# Hambmark_PCB-practice-STM32-two-wheel-ba.net
KiCad netlist of a schematic drawn in Altium Designer
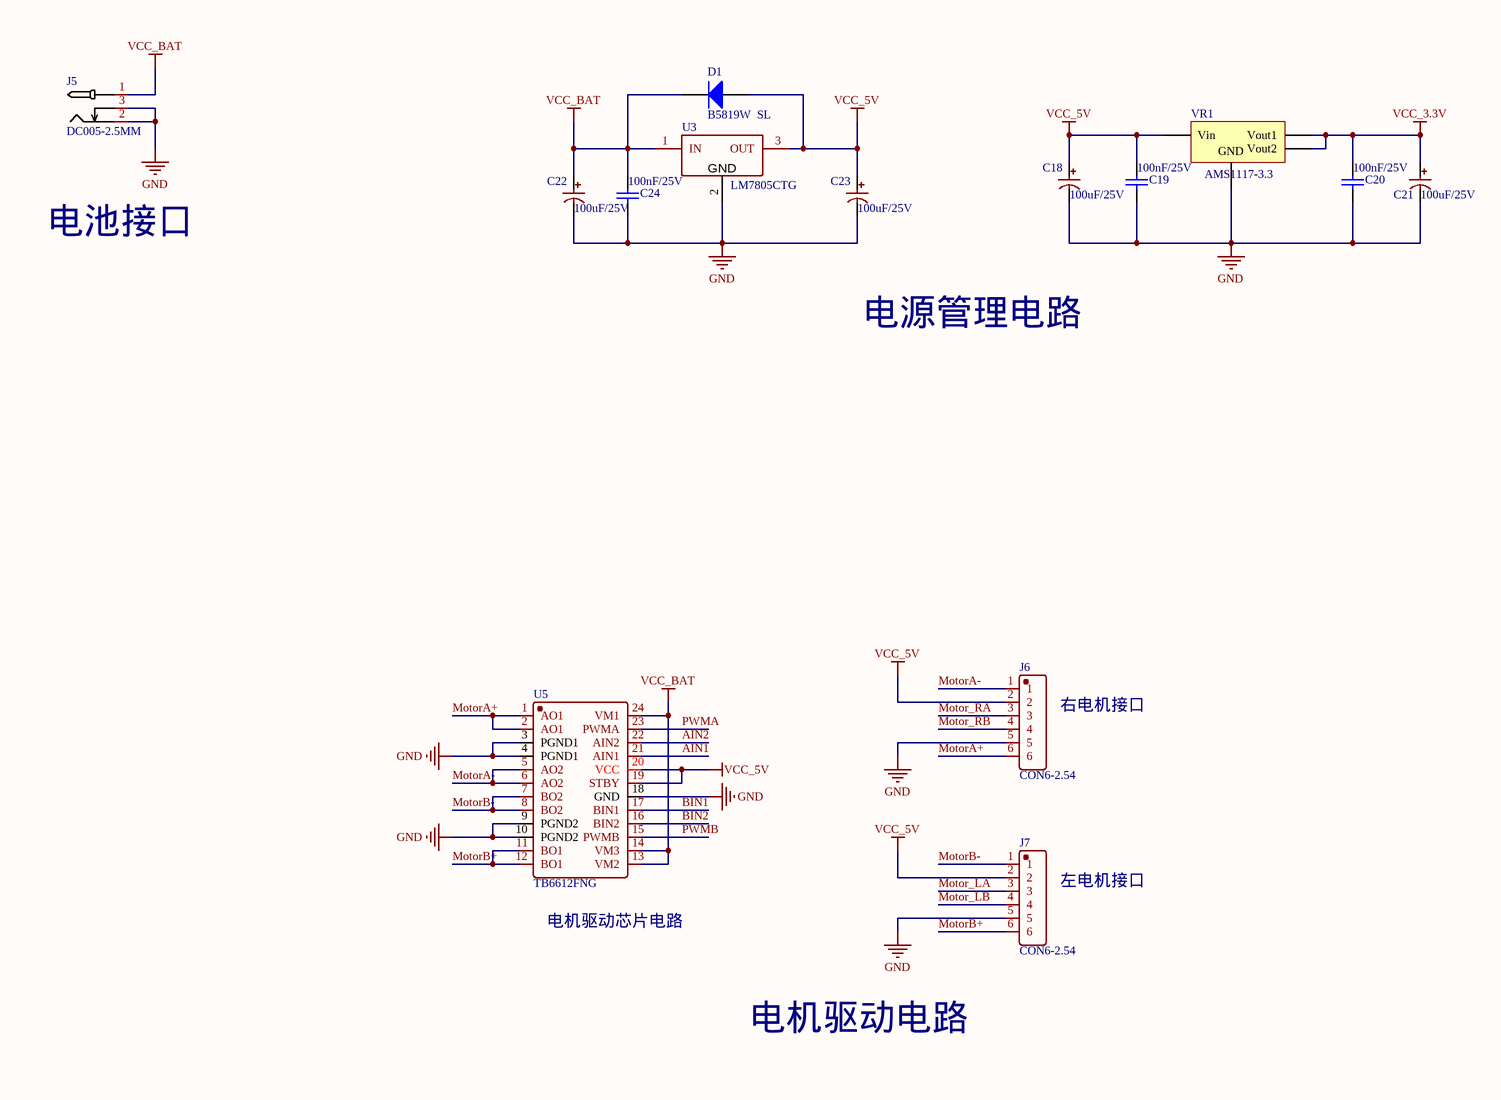
[diagram p0: Hambmark_PCB-practice-STM32-two-wheel-balancing-car__PRJ__1_Power.SchDoc]

(export (version "E")
  (design (tool "Eeschema 10.0.6"))
  (components
    (comp (ref "C18") (value "100uF/25V") (footprint "C0603") (libsource (lib "Other") (part "100uF/25V")))
    (comp (ref "C19")
      (value "100nF/25V")
      (footprint "C0603")
      (description "贴片电容")
      (libsource (lib "Cap") (part "0805 100nF(104) 10% 50V"))
    )
    (comp (ref "C20")
      (value "100nF/25V")
      (footprint "C0603")
      (description "贴片电容")
      (libsource (lib "Cap") (part "0805 100nF(104) 10% 50V"))
    )
    (comp (ref "C21") (value "100uF/25V") (footprint "C0603") (libsource (lib "Other") (part "100uF/25V")))
    (comp (ref "C22") (value "100uF/25V") (footprint "C0603") (libsource (lib "Other") (part "100uF/25V")))
    (comp (ref "C23") (value "100uF/25V") (footprint "C0603") (libsource (lib "Other") (part "100uF/25V")))
    (comp (ref "C24")
      (value "100nF/25V")
      (footprint "C0603")
      (description "贴片电容")
      (libsource (lib "Cap") (part "0805 100nF(104) 10% 50V"))
    )
    (comp (ref "D1")
      (value "B5819W  SL")
      (footprint "SOD-123")
      (description "肖特基二极管")
      (libsource (lib "Diode") (part "SOD-123 B5819W  SL"))
    )
    (comp (ref "J5")
      (value "DC005-2.5MM")
      (footprint "DC-IN-TH_DC005")
      (libsource (lib "Other") (part "DC005-2.5MM"))
    )
    (comp (ref "J6")
      (value "CON6-2.54")
      (footprint "HDR-TH_6P-P2.54-V-M")
      (libsource (lib "Other") (part "CON6-2.54"))
    )
    (comp (ref "J7")
      (value "CON6-2.54")
      (footprint "HDR-TH_6P-P2.54-V-M")
      (libsource (lib "Other") (part "CON6-2.54"))
    )
    (comp (ref "U3")
      (value "LM7805CTG")
      (footprint "TO-220-3_L10.2-W4.5-P2.54-L")
      (libsource (lib "Other") (part "LM7805CTG"))
    )
    (comp (ref "U5")
      (value "TB6612FNG")
      (footprint "SSOP-24_L8.4-W5.8-P0.65-LS7.8-BL")
      (libsource (lib "Other") (part "TB6612FNG"))
    )
    (comp (ref "VR1")
      (value "AMS1117-3.3")
      (footprint "SOT-223")
      (description "低压差线性稳压(LDO)")
      (libsource (lib "LDO") (part "SOT-223 AMS1117-3.3"))
    )
  )
  (nets
    (net (code "1") (name "/AIN1") (class "Default")
      (node (ref "U5") (pin "21") (pinfunction "AIN1_21") (pintype "passive"))
    )
    (net (code "2") (name "/AIN2") (class "Default")
      (node (ref "U5") (pin "22") (pinfunction "AIN2_22") (pintype "passive"))
    )
    (net (code "3") (name "/BIN1") (class "Default")
      (node (ref "U5") (pin "17") (pinfunction "BIN1_17") (pintype "passive"))
    )
    (net (code "4") (name "/BIN2") (class "Default")
      (node (ref "U5") (pin "16") (pinfunction "BIN2_16") (pintype "passive"))
    )
    (net (code "5") (name "/MotorA+") (class "Default")
      (node (ref "J6") (pin "6") (pinfunction "6_6") (pintype "passive"))
      (node (ref "U5") (pin "1") (pinfunction "AO1_1") (pintype "passive"))
      (node (ref "U5") (pin "2") (pinfunction "AO1_2") (pintype "passive"))
    )
    (net (code "6") (name "/MotorA-") (class "Default")
      (node (ref "J6") (pin "1") (pinfunction "1_1") (pintype "passive"))
      (node (ref "U5") (pin "5") (pinfunction "AO2_5") (pintype "passive"))
      (node (ref "U5") (pin "6") (pinfunction "AO2_6") (pintype "passive"))
    )
    (net (code "7") (name "/MotorB+") (class "Default")
      (node (ref "J7") (pin "6") (pinfunction "6_6") (pintype "passive"))
      (node (ref "U5") (pin "11") (pinfunction "BO1_11") (pintype "passive"))
      (node (ref "U5") (pin "12") (pinfunction "BO1_12") (pintype "passive"))
    )
    (net (code "8") (name "/MotorB-") (class "Default")
      (node (ref "J7") (pin "1") (pinfunction "1_1") (pintype "passive"))
      (node (ref "U5") (pin "7") (pinfunction "BO2_7") (pintype "passive"))
      (node (ref "U5") (pin "8") (pinfunction "BO2_8") (pintype "passive"))
    )
    (net (code "9") (name "/Motor_LA") (class "Default")
      (node (ref "J7") (pin "3") (pinfunction "3_3") (pintype "passive"))
    )
    (net (code "10") (name "/Motor_LB") (class "Default")
      (node (ref "J7") (pin "4") (pinfunction "4_4") (pintype "passive"))
    )
    (net (code "11") (name "/Motor_RA") (class "Default")
      (node (ref "J6") (pin "3") (pinfunction "3_3") (pintype "passive"))
    )
    (net (code "12") (name "/Motor_RB") (class "Default")
      (node (ref "J6") (pin "4") (pinfunction "4_4") (pintype "passive"))
    )
    (net (code "13") (name "/PWMA") (class "Default")
      (node (ref "U5") (pin "23") (pinfunction "PWMA_23") (pintype "passive"))
    )
    (net (code "14") (name "/PWMB") (class "Default")
      (node (ref "U5") (pin "15") (pinfunction "PWMB_15") (pintype "passive"))
    )
    (net (code "15") (name "GND") (class "Default")
      (node (ref "C18") (pin "2") (pinfunction "2_2") (pintype "passive"))
      (node (ref "C19") (pin "1") (pinfunction "1_1") (pintype "passive"))
      (node (ref "C20") (pin "1") (pinfunction "1_1") (pintype "passive"))
      (node (ref "C21") (pin "2") (pinfunction "2_2") (pintype "passive"))
      (node (ref "C22") (pin "2") (pinfunction "2_2") (pintype "passive"))
      (node (ref "C23") (pin "2") (pinfunction "2_2") (pintype "passive"))
      (node (ref "C24") (pin "1") (pinfunction "1_1") (pintype "passive"))
      (node (ref "J5") (pin "2") (pinfunction "2_2") (pintype "passive"))
      (node (ref "J5") (pin "3") (pinfunction "3_3") (pintype "passive"))
      (node (ref "J6") (pin "5") (pinfunction "5_5") (pintype "passive"))
      (node (ref "J7") (pin "5") (pinfunction "5_5") (pintype "passive"))
      (node (ref "U3") (pin "2") (pinfunction "GND_2") (pintype "passive"))
      (node (ref "U5") (pin "10") (pinfunction "PGND2_10") (pintype "passive"))
      (node (ref "U5") (pin "18") (pinfunction "GND_18") (pintype "passive"))
      (node (ref "U5") (pin "3") (pinfunction "PGND1_3") (pintype "passive"))
      (node (ref "U5") (pin "4") (pinfunction "PGND1_4") (pintype "passive"))
      (node (ref "U5") (pin "9") (pinfunction "PGND2_9") (pintype "passive"))
      (node (ref "VR1") (pin "1") (pinfunction "GND_1") (pintype "passive"))
    )
    (net (code "16") (name "VCC_3.3V") (class "Default")
      (node (ref "C20") (pin "2") (pinfunction "2_2") (pintype "passive"))
      (node (ref "C21") (pin "1") (pinfunction "1_1") (pintype "passive"))
      (node (ref "VR1") (pin "2") (pinfunction "Vout1_2") (pintype "passive"))
      (node (ref "VR1") (pin "4") (pinfunction "Vout2_4") (pintype "passive"))
    )
    (net (code "17") (name "VCC_5V") (class "Default")
      (node (ref "C18") (pin "1") (pinfunction "1_1") (pintype "passive"))
      (node (ref "C19") (pin "2") (pinfunction "2_2") (pintype "passive"))
      (node (ref "C23") (pin "1") (pinfunction "1_1") (pintype "passive"))
      (node (ref "D1") (pin "1") (pinfunction "A_1") (pintype "passive"))
      (node (ref "J6") (pin "2") (pinfunction "2_2") (pintype "passive"))
      (node (ref "J7") (pin "2") (pinfunction "2_2") (pintype "passive"))
      (node (ref "U3") (pin "3") (pinfunction "OUT_3") (pintype "passive"))
      (node (ref "U5") (pin "19") (pinfunction "STBY_19") (pintype "passive"))
      (node (ref "U5") (pin "20") (pinfunction "VCC_20") (pintype "passive"))
      (node (ref "VR1") (pin "3") (pinfunction "Vin_3") (pintype "passive"))
    )
    (net (code "18") (name "VCC_BAT") (class "Default")
      (node (ref "C22") (pin "1") (pinfunction "1_1") (pintype "passive"))
      (node (ref "C24") (pin "2") (pinfunction "2_2") (pintype "passive"))
      (node (ref "D1") (pin "2") (pinfunction "K_2") (pintype "passive"))
      (node (ref "J5") (pin "1") (pinfunction "1_1") (pintype "passive"))
      (node (ref "U3") (pin "1") (pinfunction "IN_1") (pintype "passive"))
      (node (ref "U5") (pin "13") (pinfunction "VM2_13") (pintype "passive"))
      (node (ref "U5") (pin "14") (pinfunction "VM3_14") (pintype "passive"))
      (node (ref "U5") (pin "24") (pinfunction "VM1_24") (pintype "passive"))
    )
  )
)
